# USB-TTL_UART.net
KiCad netlist of a schematic drawn in Altium Designer
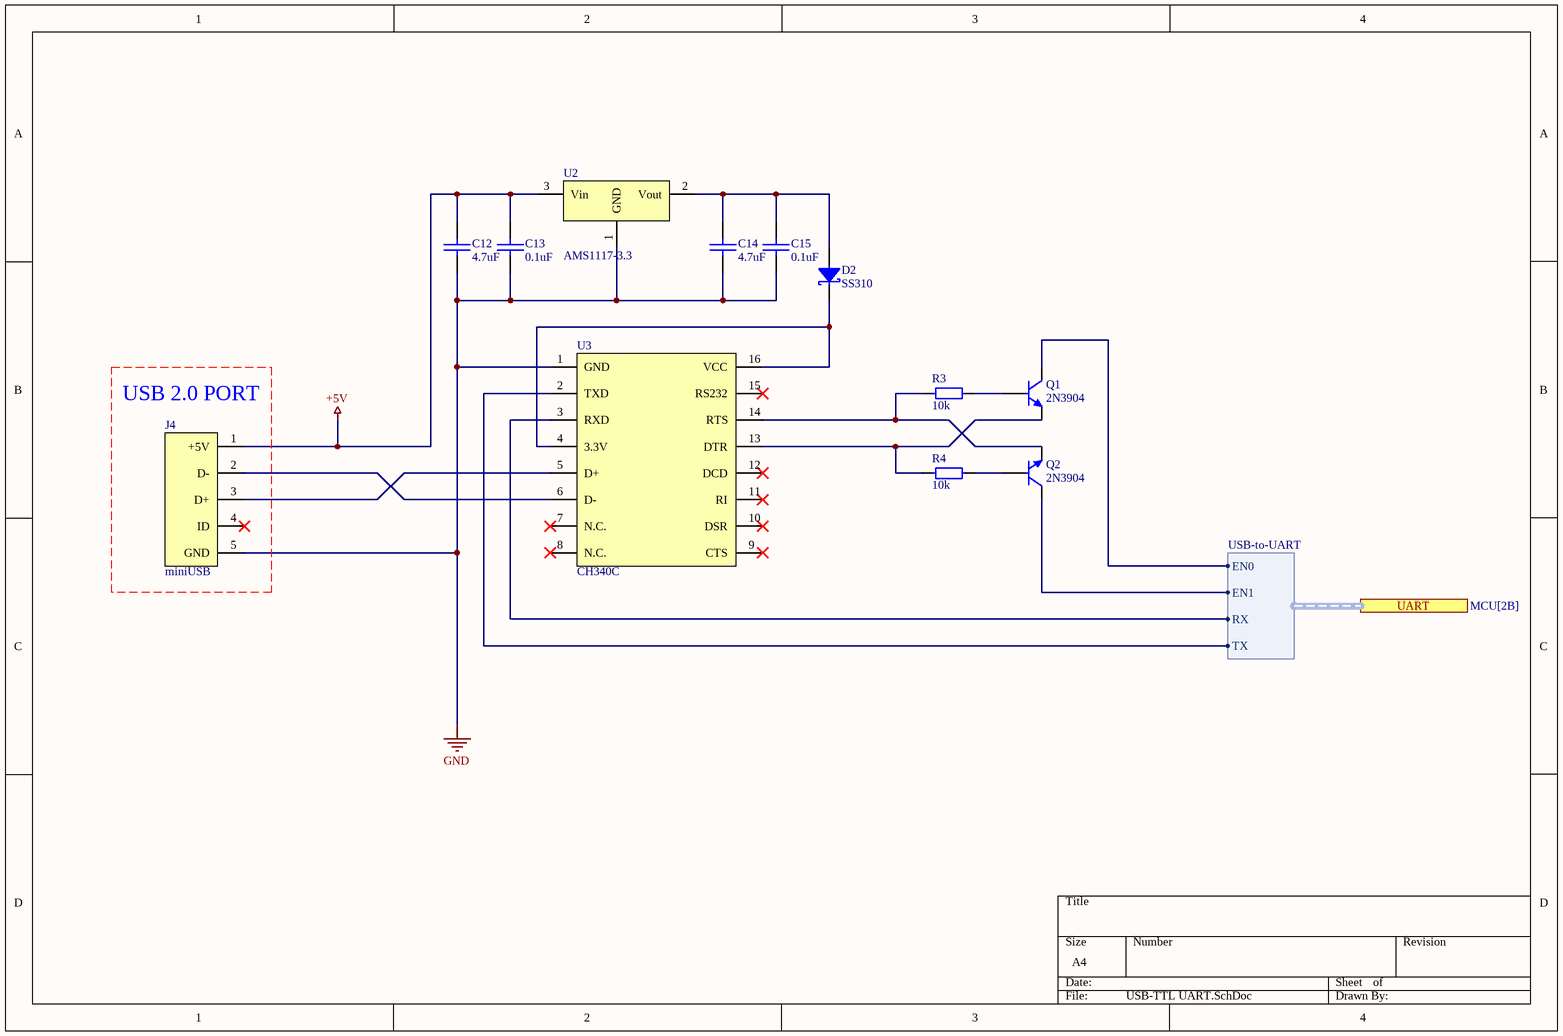
[diagram p0: USB-TTL UART.SchDoc]

(export (version "E")
  (design (tool "Eeschema 10.0.6"))
  (components
    (comp (ref "C12")
      (value "4.7uF")
      (footprint "0805 Capicator")
      (description "4.7uF X5R 10% 25V 0805")
      (fields
        (field (name "MANUFACTURER") "Murata Manufacturing")
        (field (name "PART NUMBER") "GRM21BR61E475KA12L")
      )
      (libsource (lib "BRT_Components") (part "Cap 4.7uF (0805)"))
    )
    (comp (ref "C13")
      (value "0.1uF")
      (footprint "0805 Capicator")
      (description "0.1uF X7R 25V 10% 0805")
      (fields
        (field (name "MANUFACTURER") "Murata Manufacturing")
        (field (name "PART NUMBER") "GRM21BR71E104KA01L")
      )
      (libsource (lib "BRT_Components") (part "Cap 0.1uF (0805)"))
    )
    (comp (ref "C14")
      (value "4.7uF")
      (footprint "0805 Capicator")
      (description "4.7uF X5R 10% 25V 0805")
      (fields
        (field (name "MANUFACTURER") "Murata Manufacturing")
        (field (name "PART NUMBER") "GRM21BR61E475KA12L")
      )
      (libsource (lib "BRT_Components") (part "Cap 4.7uF (0805)"))
    )
    (comp (ref "C15")
      (value "0.1uF")
      (footprint "0805 Capicator")
      (description "0.1uF X7R 25V 10% 0805")
      (fields
        (field (name "MANUFACTURER") "Murata Manufacturing")
        (field (name "PART NUMBER") "GRM21BR71E104KA01L")
      )
      (libsource (lib "BRT_Components") (part "Cap 0.1uF (0805)"))
    )
    (comp (ref "D2")
      (value "SS310")
      (footprint "DIODE: SMB")
      (description "100B 3.0A Schottky diode")
      (libsource (lib "Altium_Library") (part "Schottky diode SS310"))
    )
    (comp (ref "J4")
      (value "miniUSB")
      (footprint "miniUSB 5pin")
      (description "miniUSB 5PIN")
      (libsource (lib "Altium_Library") (part "Connector miniUSB 5pin"))
    )
    (comp (ref "Q1")
      (value "2N3904")
      (footprint "TO-92")
      (description "Transistor NPN 40V 0.2A 0.35W")
      (libsource (lib "Altium_Library") (part "Transitor NPN 2N3904"))
    )
    (comp (ref "Q2")
      (value "2N3904")
      (footprint "TO-92")
      (description "Transistor NPN 40V 0.2A 0.35W")
      (libsource (lib "Altium_Library") (part "Transitor NPN 2N3904"))
    )
    (comp (ref "R3")
      (value "10k")
      (footprint "0805 Resistor")
      (description "0.125W 0805 10k, 1%")
      (fields (field (name "PART NUMBER") "RC0805FR-0710KL") (field (name "MANUFACTURER") "Taiwan"))
      (libsource (lib "BRT_Components") (part "Res 10k (0805)"))
    )
    (comp (ref "R4")
      (value "10k")
      (footprint "0805 Resistor")
      (description "0.125W 0805 10k, 1%")
      (fields (field (name "PART NUMBER") "RC0805FR-0710KL") (field (name "MANUFACTURER") "Taiwan"))
      (libsource (lib "BRT_Components") (part "Res 10k (0805)"))
    )
    (comp (ref "U2")
      (value "AMS1117-3.3")
      (footprint "SOT-223")
      (description "1A 3.3V Low dropout voltage regulator")
      (libsource (lib "Altium_Library") (part "LDO AMS1117"))
    )
    (comp (ref "U3")
      (value "CH340C")
      (footprint "SOP-16")
      (libsource (lib "Altium_Library") (part "USB-TTL UART CH340C"))
    )
  )
  (nets
    (net (code "2") (name "+5V") (class "Default")
      (node (ref "C12") (pin "2") (pinfunction "2_2") (pintype "passive"))
      (node (ref "C13") (pin "2") (pinfunction "2_2") (pintype "passive"))
      (node (ref "J4") (pin "1") (pinfunction "+5V_1") (pintype "passive"))
      (node (ref "U2") (pin "3") (pinfunction "Vin_3") (pintype "power_in"))
    )
    (net (code "3") (name "/EN0") (class "Default")
      (node (ref "Q1") (pin "1") (pinfunction "Collector_1") (pintype "passive"))
    )
    (net (code "4") (name "/EN1") (class "Default")
      (node (ref "Q2") (pin "1") (pinfunction "Collector_1") (pintype "passive"))
    )
    (net (code "5") (name "/RX") (class "Default")
      (node (ref "U3") (pin "3") (pinfunction "RXD_3") (pintype "passive"))
    )
    (net (code "6") (name "/TX") (class "Default")
      (node (ref "U3") (pin "2") (pinfunction "TXD_2") (pintype "passive"))
    )
    (net (code "8") (name "GND") (class "Default")
      (node (ref "C12") (pin "1") (pinfunction "1_1") (pintype "passive"))
      (node (ref "C13") (pin "1") (pinfunction "1_1") (pintype "passive"))
      (node (ref "C14") (pin "1") (pinfunction "1_1") (pintype "passive"))
      (node (ref "C15") (pin "1") (pinfunction "1_1") (pintype "passive"))
      (node (ref "J4") (pin "5") (pinfunction "GND_5") (pintype "passive"))
      (node (ref "U2") (pin "1") (pinfunction "GND_1") (pintype "power_in"))
      (node (ref "U3") (pin "1") (pinfunction "GND_1") (pintype "power_in"))
    )
    (net (code "9") (name "Net-(J4-D+)") (class "Default")
      (node (ref "J4") (pin "3") (pinfunction "D+_3") (pintype "passive"))
      (node (ref "U3") (pin "5") (pinfunction "D+_5") (pintype "passive"))
    )
    (net (code "10") (name "Net-(J4-D-)") (class "Default")
      (node (ref "J4") (pin "2") (pinfunction "D-_2") (pintype "passive"))
      (node (ref "U3") (pin "6") (pinfunction "D-_6") (pintype "passive"))
    )
    (net (code "11") (name "Net-(Q1-Base)") (class "Default")
      (node (ref "Q1") (pin "2") (pinfunction "Base_2") (pintype "passive"))
      (node (ref "R3") (pin "2") (pinfunction "2_2") (pintype "passive"))
    )
    (net (code "12") (name "Net-(Q1-Emitter)") (class "Default")
      (node (ref "Q1") (pin "3") (pinfunction "Emitter_3") (pintype "passive"))
      (node (ref "R4") (pin "1") (pinfunction "1_1") (pintype "passive"))
      (node (ref "U3") (pin "13") (pinfunction "DTR_13") (pintype "passive"))
    )
    (net (code "13") (name "Net-(Q2-Base)") (class "Default")
      (node (ref "Q2") (pin "2") (pinfunction "Base_2") (pintype "passive"))
      (node (ref "R4") (pin "2") (pinfunction "2_2") (pintype "passive"))
    )
    (net (code "14") (name "Net-(Q2-Emitter)") (class "Default")
      (node (ref "Q2") (pin "3") (pinfunction "Emitter_3") (pintype "passive"))
      (node (ref "R3") (pin "1") (pinfunction "1_1") (pintype "passive"))
      (node (ref "U3") (pin "14") (pinfunction "RTS_14") (pintype "passive"))
    )
    (net (code "15") (name "Net-(U2-Vout)") (class "Default")
      (node (ref "C14") (pin "2") (pinfunction "2_2") (pintype "passive"))
      (node (ref "C15") (pin "2") (pinfunction "2_2") (pintype "passive"))
      (node (ref "D2") (pin "1") (pinfunction "1_1") (pintype "passive"))
      (node (ref "U2") (pin "2") (pinfunction "Vout_2") (pintype "power_in"))
    )
    (net (code "16") (name "Net-(U3-3.3V)") (class "Default")
      (node (ref "D2") (pin "2") (pinfunction "2_2") (pintype "passive"))
      (node (ref "U3") (pin "16") (pinfunction "VCC_16") (pintype "power_in"))
      (node (ref "U3") (pin "4") (pinfunction "3.3V_4") (pintype "power_in"))
    )
    (net (code "17") (name "unconnected-(J4-ID-Pad4)") (class "Default")
      (node (ref "J4") (pin "4") (pinfunction "ID_4") (pintype "passive+no_connect"))
    )
    (net (code "18") (name "unconnected-(U3-CTS-Pad9)") (class "Default")
      (node (ref "U3") (pin "9") (pinfunction "CTS_9") (pintype "power_in+no_connect"))
    )
    (net (code "19") (name "unconnected-(U3-DCD-Pad12)") (class "Default")
      (node (ref "U3") (pin "12") (pinfunction "DCD_12") (pintype "power_in+no_connect"))
    )
    (net (code "20") (name "unconnected-(U3-DSR-Pad10)") (class "Default")
      (node (ref "U3") (pin "10") (pinfunction "DSR_10") (pintype "passive+no_connect"))
    )
    (net (code "21") (name "unconnected-(U3-N.C.-Pad7)") (class "Default")
      (node (ref "U3") (pin "7") (pinfunction "N.C._7") (pintype "passive+no_connect"))
    )
    (net (code "22") (name "unconnected-(U3-N.C.-Pad8)") (class "Default")
      (node (ref "U3") (pin "8") (pinfunction "N.C._8") (pintype "passive+no_connect"))
    )
    (net (code "23") (name "unconnected-(U3-RI-Pad11)") (class "Default")
      (node (ref "U3") (pin "11") (pinfunction "RI_11") (pintype "passive+no_connect"))
    )
    (net (code "24") (name "unconnected-(U3-RS232-Pad15)") (class "Default")
      (node (ref "U3") (pin "15") (pinfunction "RS232_15") (pintype "passive+no_connect"))
    )
  )
)
